# KeypadNut.net
KiCad netlist of a schematic drawn in EAGLE
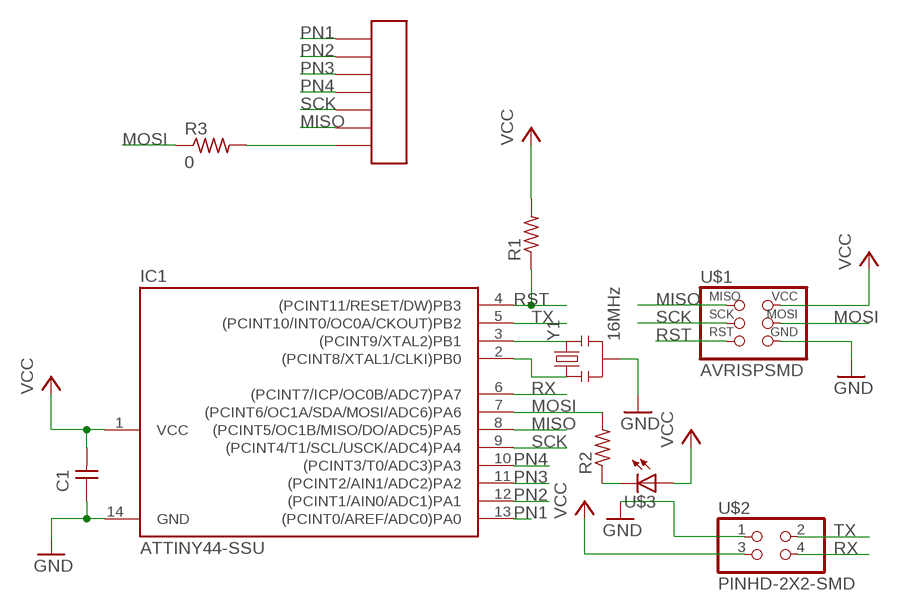
[diagram p0: schematic, sheet 1]

(export (version "E")
  (design (tool "Eeschema 10.0.6"))
  (components
    (comp (ref "C1")
      (value "UNPOLARIZED_CAPACITOR1206")
      (footprint "eagle-import:1206")
      (libsource (lib "eagle-import") (part "UNPOLARIZED_CAPACITOR1206"))
    )
    (comp (ref "IC1")
      (value "ATTINY44-SSU")
      (footprint "eagle-import:SOIC14")
      (libsource (lib "eagle-import") (part "ATTINY44-SSU"))
    )
    (comp (ref "R1")
      (value "RESISTOR1206")
      (footprint "eagle-import:1206")
      (libsource (lib "eagle-import") (part "RESISTOR1206"))
    )
    (comp (ref "R2")
      (value "RESISTOR1206")
      (footprint "eagle-import:1206")
      (libsource (lib "eagle-import") (part "RESISTOR1206"))
    )
    (comp (ref "R3")
      (value "0")
      (footprint "eagle-import:1206")
      (libsource (lib "eagle-import") (part "fablab_RESISTOR1206"))
    )
    (comp (ref "U$1")
      (value "AVRISPSMD")
      (footprint "eagle-import:2X03SMD")
      (libsource (lib "eagle-import") (part "AVRISPSMD"))
    )
    (comp (ref "U$2")
      (value "PINHD-2X2-SMD")
      (footprint "eagle-import:2X02SMD")
      (libsource (lib "eagle-import") (part "PINHD-2X2-SMD"))
    )
    (comp (ref "U$3")
      (value "LED1206")
      (footprint "eagle-import:1206")
      (libsource (lib "eagle-import") (part "LED1206"))
    )
    (comp (ref "U$4")
      (value "1X07-HEADER")
      (footprint "eagle-import:1X07-SMD")
      (libsource (lib "eagle-import") (part "1X07-HEADER"))
    )
    (comp (ref "Y1")
      (value "16MHz")
      (footprint "eagle-import:RESONATOR-SMD")
      (libsource (lib "eagle-import") (part "RESONATOR16MHZ"))
    )
  )
  (nets
    (net (code "1") (name "/MISO") (class "Default")
      (node (ref "IC1") (pin "8") (pinfunction "(PCINT5/OC1B/MISO/DO/ADC5)PA5_8") (pintype "bidirectional"))
      (node (ref "U$1") (pin "1") (pinfunction "MISO_1") (pintype "passive"))
      (node (ref "U$4") (pin "6") (pinfunction "P$6_6") (pintype "bidirectional"))
    )
    (net (code "2") (name "/MOSI") (class "Default")
      (node (ref "IC1") (pin "7") (pinfunction "(PCINT6/OC1A/SDA/MOSI/ADC6)PA6_7") (pintype "bidirectional"))
      (node (ref "R2") (pin "2") (pinfunction "2_2") (pintype "passive"))
      (node (ref "R3") (pin "1") (pinfunction "1_1") (pintype "passive"))
      (node (ref "U$1") (pin "4") (pinfunction "MOSI_4") (pintype "passive"))
    )
    (net (code "3") (name "/PN1") (class "Default")
      (node (ref "IC1") (pin "13") (pinfunction "(PCINT0/AREF/ADC0)PA0_13") (pintype "bidirectional"))
      (node (ref "U$4") (pin "1") (pinfunction "P$1_1") (pintype "bidirectional"))
    )
    (net (code "4") (name "/PN2") (class "Default")
      (node (ref "IC1") (pin "12") (pinfunction "(PCINT1/AIN0/ADC1)PA1_12") (pintype "bidirectional"))
      (node (ref "U$4") (pin "2") (pinfunction "P$2_2") (pintype "bidirectional"))
    )
    (net (code "5") (name "/PN3") (class "Default")
      (node (ref "IC1") (pin "11") (pinfunction "(PCINT2/AIN1/ADC2)PA2_11") (pintype "bidirectional"))
      (node (ref "U$4") (pin "3") (pinfunction "P$3_3") (pintype "bidirectional"))
    )
    (net (code "6") (name "/PN4") (class "Default")
      (node (ref "IC1") (pin "10") (pinfunction "(PCINT3/T0/ADC3)PA3_10") (pintype "bidirectional"))
      (node (ref "U$4") (pin "4") (pinfunction "P$4_4") (pintype "bidirectional"))
    )
    (net (code "7") (name "/RST") (class "Default")
      (node (ref "IC1") (pin "4") (pinfunction "(PCINT11/RESET/DW)PB3_4") (pintype "bidirectional"))
      (node (ref "R1") (pin "1") (pinfunction "1_1") (pintype "passive"))
      (node (ref "U$1") (pin "5") (pinfunction "RST_5") (pintype "passive"))
    )
    (net (code "8") (name "/RX") (class "Default")
      (node (ref "IC1") (pin "6") (pinfunction "(PCINT7/ICP/OC0B/ADC7)PA7_6") (pintype "bidirectional"))
      (node (ref "U$2") (pin "4") (pinfunction "4_4") (pintype "passive"))
    )
    (net (code "9") (name "/SCK") (class "Default")
      (node (ref "IC1") (pin "9") (pinfunction "(PCINT4/T1/SCL/USCK/ADC4)PA4_9") (pintype "bidirectional"))
      (node (ref "U$1") (pin "3") (pinfunction "SCK_3") (pintype "passive"))
      (node (ref "U$4") (pin "5") (pinfunction "P$5_5") (pintype "bidirectional"))
    )
    (net (code "10") (name "/TX") (class "Default")
      (node (ref "IC1") (pin "5") (pinfunction "(PCINT10/INT0/OC0A/CKOUT)PB2_5") (pintype "bidirectional"))
      (node (ref "U$2") (pin "2") (pinfunction "2_2") (pintype "passive"))
    )
    (net (code "11") (name "GND") (class "Default")
      (node (ref "C1") (pin "1") (pinfunction "1_1") (pintype "passive"))
      (node (ref "IC1") (pin "14") (pinfunction "GND_14") (pintype "power_in"))
      (node (ref "U$1") (pin "6") (pinfunction "GND_6") (pintype "passive"))
      (node (ref "U$2") (pin "1") (pinfunction "1_1") (pintype "passive"))
      (node (ref "Y1") (pin "2") (pinfunction "2_2") (pintype "passive"))
    )
    (net (code "12") (name "Net-(IC1-(PCINT8{slash}XTAL1{slash}CLKI)PB0)") (class "Default")
      (node (ref "IC1") (pin "2") (pinfunction "(PCINT8/XTAL1/CLKI)PB0_2") (pintype "bidirectional"))
      (node (ref "Y1") (pin "1") (pinfunction "1_1") (pintype "passive"))
    )
    (net (code "13") (name "Net-(IC1-(PCINT9{slash}XTAL2)PB1)") (class "Default")
      (node (ref "IC1") (pin "3") (pinfunction "(PCINT9/XTAL2)PB1_3") (pintype "bidirectional"))
      (node (ref "Y1") (pin "3") (pinfunction "3_3") (pintype "passive"))
    )
    (net (code "14") (name "Net-(U$3-C)") (class "Default")
      (node (ref "R2") (pin "1") (pinfunction "1_1") (pintype "passive"))
      (node (ref "U$3") (pin "2") (pinfunction "C_2") (pintype "passive"))
    )
    (net (code "15") (name "Net-(U$4-P$7)") (class "Default")
      (node (ref "R3") (pin "2") (pinfunction "2_2") (pintype "passive"))
      (node (ref "U$4") (pin "7") (pinfunction "P$7_7") (pintype "bidirectional"))
    )
    (net (code "16") (name "VCC") (class "Default")
      (node (ref "C1") (pin "2") (pinfunction "2_2") (pintype "passive"))
      (node (ref "IC1") (pin "1") (pinfunction "VCC_1") (pintype "power_in"))
      (node (ref "R1") (pin "2") (pinfunction "2_2") (pintype "passive"))
      (node (ref "U$1") (pin "2") (pinfunction "VCC_2") (pintype "passive"))
      (node (ref "U$2") (pin "3") (pinfunction "3_3") (pintype "passive"))
      (node (ref "U$3") (pin "1") (pinfunction "A_1") (pintype "passive"))
    )
  )
)
